# Adafruit_Feather_M4_Express.net
KiCad netlist of a schematic drawn in EAGLE
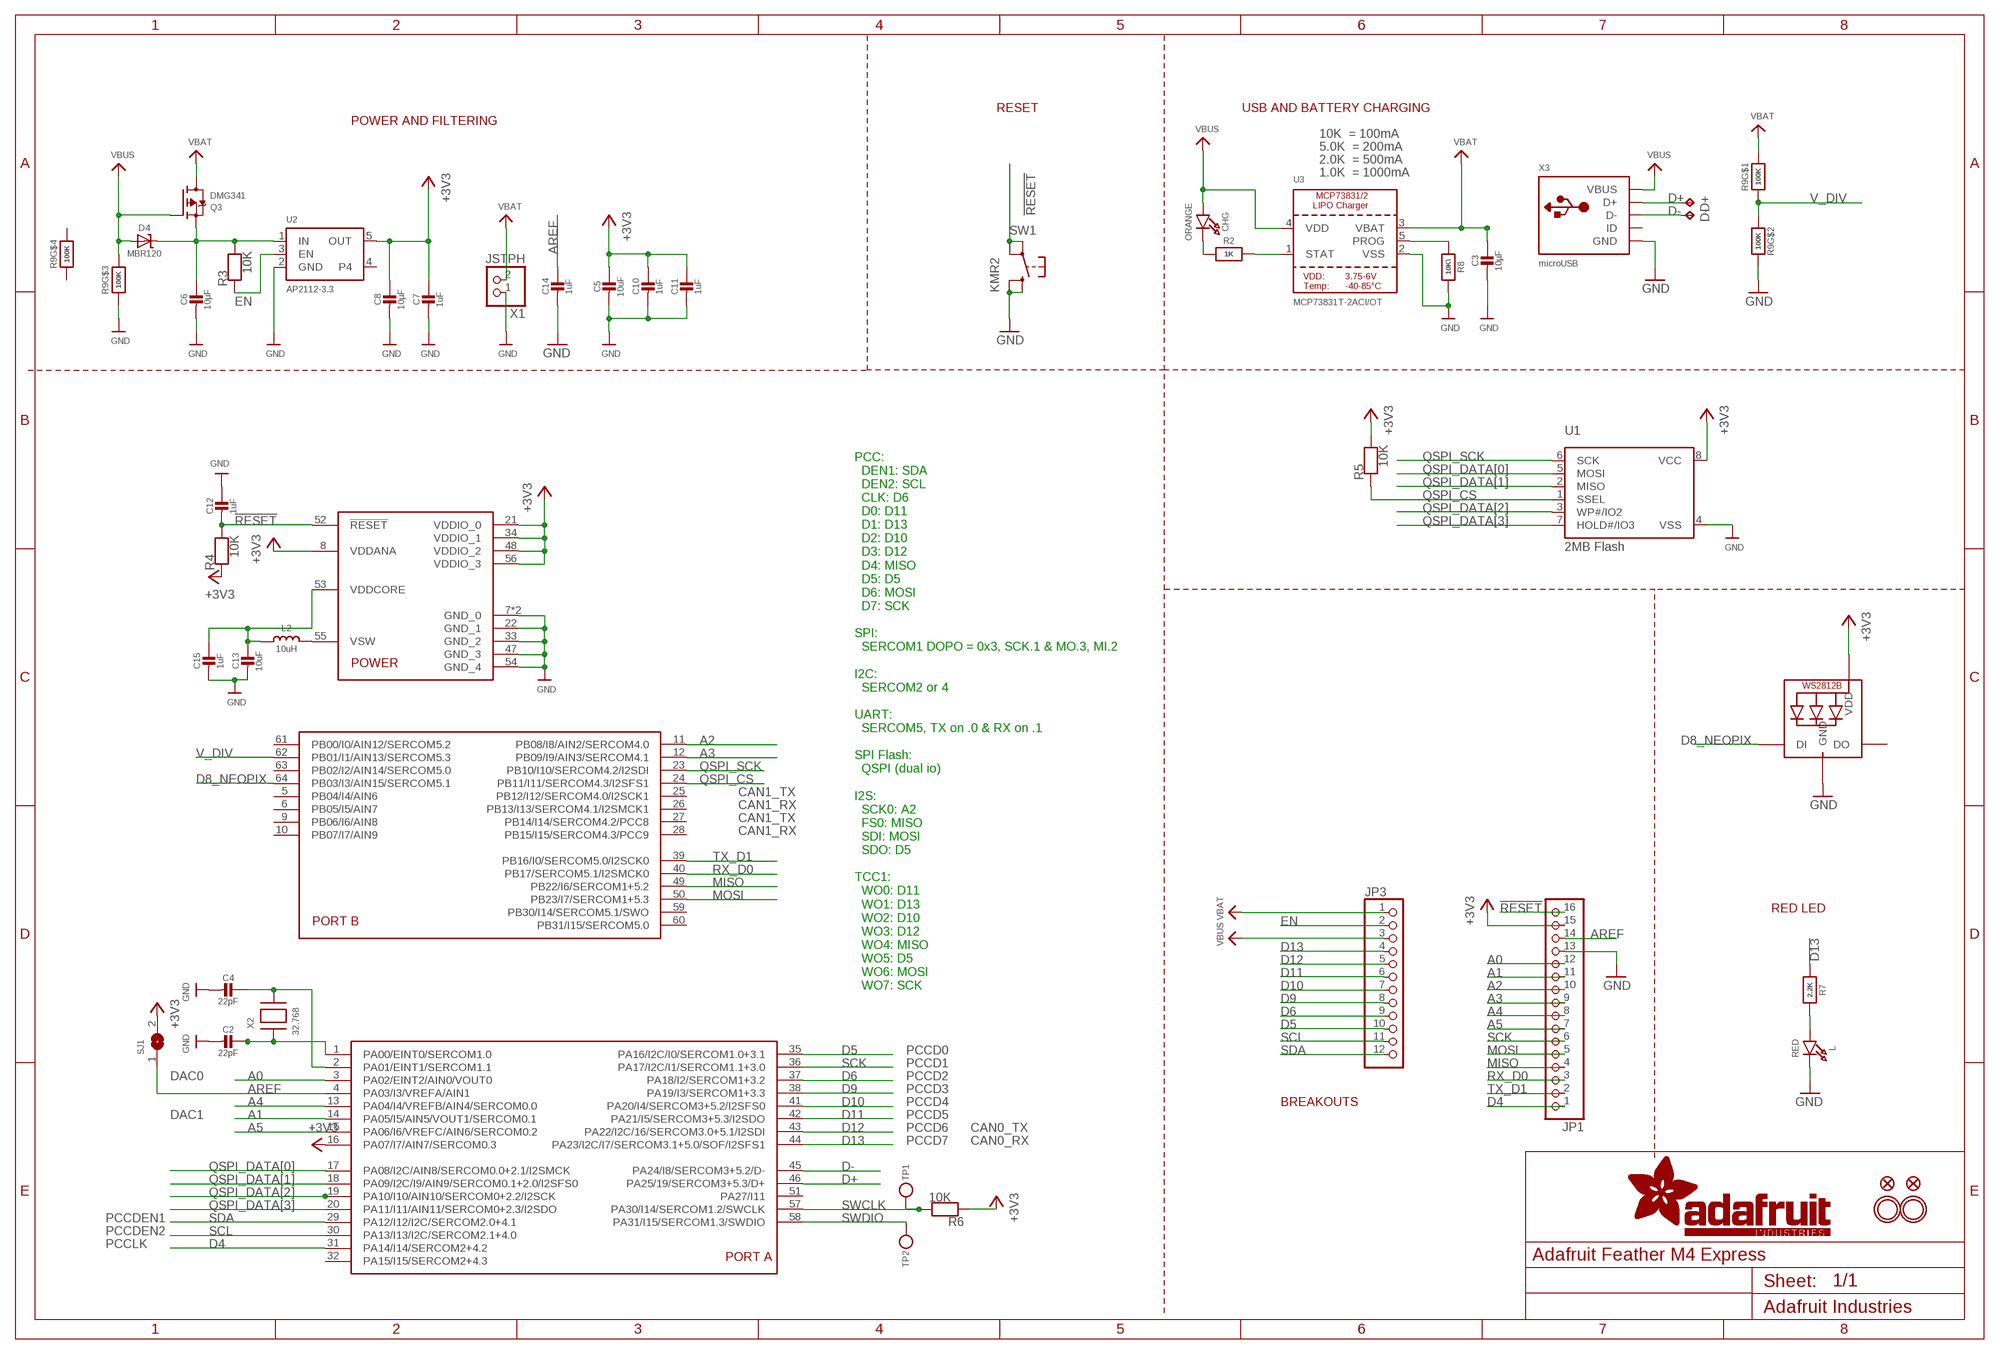
[diagram p0: schematic, sheet 1]

(export (version "E")
  (design (tool "Eeschema 10.0.6"))
  (components
    (comp (ref "C2")
      (value "22pF")
      (footprint "eagle-import:0603-NO")
      (libsource (lib "eagle-import") (part "CAP_CERAMIC0603_NO"))
    )
    (comp (ref "C3")
      (value "10µF")
      (footprint "eagle-import:0805-NO")
      (libsource (lib "eagle-import") (part "CAP_CERAMIC0805-NOOUTLINE"))
    )
    (comp (ref "C4")
      (value "22pF")
      (footprint "eagle-import:0603-NO")
      (libsource (lib "eagle-import") (part "CAP_CERAMIC0603_NO"))
    )
    (comp (ref "C5")
      (value "10uF")
      (footprint "eagle-import:0805-NO")
      (libsource (lib "eagle-import") (part "CAP_CERAMIC0805-NOOUTLINE"))
    )
    (comp (ref "C6")
      (value "10µF")
      (footprint "eagle-import:0805-NO")
      (libsource (lib "eagle-import") (part "CAP_CERAMIC0805-NOOUTLINE"))
    )
    (comp (ref "C7")
      (value "1uF")
      (footprint "eagle-import:0603-NO")
      (libsource (lib "eagle-import") (part "CAP_CERAMIC0603_NO"))
    )
    (comp (ref "C8")
      (value "10µF")
      (footprint "eagle-import:0805-NO")
      (libsource (lib "eagle-import") (part "CAP_CERAMIC0805-NOOUTLINE"))
    )
    (comp (ref "C10")
      (value "1uF")
      (footprint "eagle-import:0603-NO")
      (libsource (lib "eagle-import") (part "CAP_CERAMIC0603_NO"))
    )
    (comp (ref "C11")
      (value "1uF")
      (footprint "eagle-import:0603-NO")
      (libsource (lib "eagle-import") (part "CAP_CERAMIC0603_NO"))
    )
    (comp (ref "C12")
      (value "1uF")
      (footprint "eagle-import:0603-NO")
      (libsource (lib "eagle-import") (part "CAP_CERAMIC0603_NO"))
    )
    (comp (ref "C13")
      (value "10uF")
      (footprint "eagle-import:0805-NO")
      (libsource (lib "eagle-import") (part "CAP_CERAMIC0805-NOOUTLINE"))
    )
    (comp (ref "C14")
      (value "1uF")
      (footprint "eagle-import:0603-NO")
      (libsource (lib "eagle-import") (part "CAP_CERAMIC0603_NO"))
    )
    (comp (ref "C15")
      (value "1uF")
      (footprint "eagle-import:0603-NO")
      (libsource (lib "eagle-import") (part "CAP_CERAMIC0603_NO"))
    )
    (comp (ref "CHG")
      (value "ORANGE")
      (footprint "eagle-import:CHIPLED_0805_NOOUTLINE")
      (libsource (lib "eagle-import") (part "LED0805_NOOUTLINE"))
    )
    (comp (ref "D+")
      (value "TPB1,27")
      (footprint "eagle-import:B1,27")
      (libsource (lib "eagle-import") (part "TPB1,27"))
    )
    (comp (ref "D-")
      (value "TPB1,27")
      (footprint "eagle-import:B1,27")
      (libsource (lib "eagle-import") (part "TPB1,27"))
    )
    (comp (ref "D4")
      (value "MBR120")
      (footprint "eagle-import:SOD-123")
      (libsource (lib "eagle-import") (part "DIODE-SCHOTTKYSOD-123"))
    )
    (comp (ref "JP1")
      (value "HEADER-1X16ROUND")
      (footprint "eagle-import:1X16_ROUND")
      (libsource (lib "eagle-import") (part "HEADER-1X16ROUND"))
    )
    (comp (ref "JP3")
      (value "HEADER-1X12")
      (footprint "eagle-import:1X12_ROUND")
      (libsource (lib "eagle-import") (part "HEADER-1X12"))
    )
    (comp (ref "L")
      (value "RED")
      (footprint "eagle-import:CHIPLED_0805_NOOUTLINE")
      (libsource (lib "eagle-import") (part "LED0805_NOOUTLINE"))
    )
    (comp (ref "L2")
      (value "10uH")
      (footprint "eagle-import:INDUCTOR_1007")
      (libsource (lib "eagle-import") (part "INDUCTOR"))
    )
    (comp (ref "LED1")
      (value "WS2812B3535")
      (footprint "eagle-import:LED3535")
      (libsource (lib "eagle-import") (part "WS2812B3535"))
    )
    (comp (ref "Q3")
      (value "DMG341")
      (footprint "eagle-import:SOT23-R")
      (libsource (lib "eagle-import") (part "MOSFET-P"))
    )
    (comp (ref "R2")
      (value "1K")
      (footprint "eagle-import:0603-NO")
      (libsource (lib "eagle-import") (part "RESISTOR_0603_NOOUT"))
    )
    (comp (ref "R3")
      (value "10K")
      (footprint "eagle-import:0603-NO")
      (libsource (lib "eagle-import") (part "RESISTOR_0603_NOOUT"))
    )
    (comp (ref "R4")
      (value "10K")
      (footprint "eagle-import:0603-NO")
      (libsource (lib "eagle-import") (part "RESISTOR_0603_NOOUT"))
    )
    (comp (ref "R5")
      (value "10K")
      (footprint "eagle-import:0603-NO")
      (libsource (lib "eagle-import") (part "RESISTOR_0603_NOOUT"))
    )
    (comp (ref "R6")
      (value "10K")
      (footprint "eagle-import:0603-NO")
      (libsource (lib "eagle-import") (part "RESISTOR_0603_NOOUT"))
    )
    (comp (ref "R7")
      (value "2.2K")
      (footprint "eagle-import:0603-NO")
      (libsource (lib "eagle-import") (part "RESISTOR_0603_NOOUT"))
    )
    (comp (ref "R8")
      (value "10K\\")
      (footprint "eagle-import:0603-NO")
      (libsource (lib "eagle-import") (part "RESISTOR_0603_NOOUT"))
    )
    (comp (ref "R9")
      (value "100K")
      (footprint "eagle-import:RESPACK_4X0603_NO")
      (libsource (lib "eagle-import") (part "RESISTOR_4PACK_NO"))
    )
    (comp (ref "SJ1")
      (value "SOLDERJUMPERCLOSED")
      (footprint "eagle-import:SOLDERJUMPER_CLOSEDWIRE")
      (libsource (lib "eagle-import") (part "SOLDERJUMPERCLOSED"))
    )
    (comp (ref "SW1")
      (value "KMR2")
      (footprint "eagle-import:BTN_KMR2_4.6X2.8")
      (libsource (lib "eagle-import") (part "SWITCH_TACT_SMT4.6X2.8"))
    )
    (comp (ref "TP1")
      (value "TESTPOINTROUND1.5MM")
      (footprint "eagle-import:TESTPOINT_ROUND_1.5MM")
      (libsource (lib "eagle-import") (part "TESTPOINTROUND1.5MM"))
    )
    (comp (ref "TP2")
      (value "TESTPOINTROUND1.5MM")
      (footprint "eagle-import:TESTPOINT_ROUND_1.5MM")
      (libsource (lib "eagle-import") (part "TESTPOINTROUND1.5MM"))
    )
    (comp (ref "U$14")
      (value "ATSAMD51J")
      (footprint "eagle-import:PQFN64-1")
      (libsource (lib "eagle-import") (part "ATSAMD51J"))
    )
    (comp (ref "U$31")
      (value "MOUNTINGHOLE2.5")
      (footprint "eagle-import:MOUNTINGHOLE_2.5_PLATED")
      (libsource (lib "eagle-import") (part "MOUNTINGHOLE2.5"))
    )
    (comp (ref "U$32")
      (value "MOUNTINGHOLE2.5")
      (footprint "eagle-import:MOUNTINGHOLE_2.5_PLATED")
      (libsource (lib "eagle-import") (part "MOUNTINGHOLE2.5"))
    )
    (comp (ref "U$34")
      (value "FIDUCIAL_1MM")
      (footprint "eagle-import:FIDUCIAL_1MM")
      (libsource (lib "eagle-import") (part "FIDUCIAL_1MM"))
    )
    (comp (ref "U$35")
      (value "FIDUCIAL_1MM")
      (footprint "eagle-import:FIDUCIAL_1MM")
      (libsource (lib "eagle-import") (part "FIDUCIAL_1MM"))
    )
    (comp (ref "U1")
      (value "2MB Flash")
      (footprint "eagle-import:USON8")
      (libsource (lib "eagle-import") (part "SPIFLASH_8PINUX"))
    )
    (comp (ref "U2")
      (value "AP2112-3.3")
      (footprint "eagle-import:SOT23-5")
      (libsource (lib "eagle-import") (part "VREG_SOT23-5"))
    )
    (comp (ref "U3")
      (value "MCP73831T-2ACI/OT")
      (footprint "eagle-import:SOT23-5")
      (libsource (lib "eagle-import") (part "MCP73831/2"))
    )
    (comp (ref "X1")
      (value "JSTPH")
      (footprint "eagle-import:JSTPH2")
      (libsource (lib "eagle-import") (part "CON_JST_PH_2PIN"))
    )
    (comp (ref "X2")
      (value "32.768")
      (footprint "eagle-import:XTAL3215")
      (libsource (lib "eagle-import") (part "XTAL-3.2X1.5"))
    )
    (comp (ref "X3")
      (value "microUSB")
      (footprint "eagle-import:4UCONN_20329_V2")
      (libsource (lib "eagle-import") (part "USB_MICRO_20329_V2"))
    )
  )
  (nets
    (net (code "1") (name "+3V3") (class "Default")
      (node (ref "C10") (pin "1") (pinfunction "1_1") (pintype "passive"))
      (node (ref "C11") (pin "1") (pinfunction "1_1") (pintype "passive"))
      (node (ref "C5") (pin "1") (pinfunction "1_1") (pintype "passive"))
      (node (ref "C7") (pin "1") (pinfunction "1_1") (pintype "passive"))
      (node (ref "C8") (pin "1") (pinfunction "1_1") (pintype "passive"))
      (node (ref "JP1") (pin "15") (pinfunction "15_15") (pintype "passive"))
      (node (ref "LED1") (pin "2") (pinfunction "VDD_2") (pintype "power_in"))
      (node (ref "R4") (pin "1") (pinfunction "1_1") (pintype "passive"))
      (node (ref "R5") (pin "2") (pinfunction "2_2") (pintype "passive"))
      (node (ref "R6") (pin "1") (pinfunction "1_1") (pintype "passive"))
      (node (ref "SJ1") (pin "2") (pinfunction "2_2") (pintype "passive"))
      (node (ref "U$14") (pin "16") (pinfunction "PA07/I7/AIN7/SERCOM0.3_16") (pintype "bidirectional"))
      (node (ref "U$14") (pin "21") (pinfunction "VDDIO_0_21") (pintype "bidirectional"))
      (node (ref "U$14") (pin "34") (pinfunction "VDDIO_1_34") (pintype "bidirectional"))
      (node (ref "U$14") (pin "48") (pinfunction "VDDIO_2_48") (pintype "bidirectional"))
      (node (ref "U$14") (pin "56") (pinfunction "VDDIO_3_56") (pintype "bidirectional"))
      (node (ref "U$14") (pin "8") (pinfunction "VDDANA_8") (pintype "bidirectional"))
      (node (ref "U1") (pin "8") (pinfunction "VCC_8") (pintype "bidirectional"))
      (node (ref "U2") (pin "5") (pinfunction "OUT_5") (pintype "power_in"))
    )
    (net (code "2") (name "/A0") (class "Default")
      (node (ref "JP1") (pin "12") (pinfunction "12_12") (pintype "passive"))
      (node (ref "U$14") (pin "3") (pinfunction "PA02/EINT2/AIN0/VOUT0_3") (pintype "bidirectional"))
    )
    (net (code "3") (name "/A1") (class "Default")
      (node (ref "JP1") (pin "11") (pinfunction "11_11") (pintype "passive"))
      (node (ref "U$14") (pin "14") (pinfunction "PA05/I5/AIN5/VOUT1/SERCOM0.1_14") (pintype "bidirectional"))
    )
    (net (code "4") (name "/A2") (class "Default")
      (node (ref "JP1") (pin "10") (pinfunction "10_10") (pintype "passive"))
      (node (ref "U$14") (pin "11") (pinfunction "PB08/I8/AIN2/SERCOM4.0_11") (pintype "bidirectional"))
    )
    (net (code "5") (name "/A3") (class "Default")
      (node (ref "JP1") (pin "9") (pinfunction "9_9") (pintype "passive"))
      (node (ref "U$14") (pin "12") (pinfunction "PB09/I9/AIN3/SERCOM4.1_12") (pintype "bidirectional"))
    )
    (net (code "6") (name "/A4") (class "Default")
      (node (ref "JP1") (pin "8") (pinfunction "8_8") (pintype "passive"))
      (node (ref "U$14") (pin "13") (pinfunction "PA04/I4/VREFB/AIN4/SERCOM0.0_13") (pintype "bidirectional"))
    )
    (net (code "7") (name "/A5") (class "Default")
      (node (ref "JP1") (pin "7") (pinfunction "7_7") (pintype "passive"))
      (node (ref "U$14") (pin "15") (pinfunction "PA06/I6/VREFC/AIN6/SERCOM0.2_15") (pintype "bidirectional"))
    )
    (net (code "8") (name "/AREF") (class "Default")
      (node (ref "C14") (pin "1") (pinfunction "1_1") (pintype "passive"))
      (node (ref "JP1") (pin "14") (pinfunction "14_14") (pintype "passive"))
      (node (ref "SJ1") (pin "1") (pinfunction "1_1") (pintype "passive"))
      (node (ref "U$14") (pin "4") (pinfunction "PA03/I3/VREFA/AIN1_4") (pintype "bidirectional"))
    )
    (net (code "9") (name "/D+") (class "Default")
      (node (ref "D+") (pin "TP") (pinfunction "TP_TP") (pintype "input"))
      (node (ref "U$14") (pin "46") (pinfunction "PA25/19/SERCOM3+5.3/D+_46") (pintype "bidirectional"))
      (node (ref "X3") (pin "D+") (pinfunction "D+_D+") (pintype "bidirectional"))
    )
    (net (code "10") (name "/D-") (class "Default")
      (node (ref "D-") (pin "TP") (pinfunction "TP_TP") (pintype "input"))
      (node (ref "U$14") (pin "45") (pinfunction "PA24/I8/SERCOM3+5.2/D-_45") (pintype "bidirectional"))
      (node (ref "X3") (pin "D-") (pinfunction "D-_D-") (pintype "bidirectional"))
    )
    (net (code "11") (name "/D4") (class "Default")
      (node (ref "JP1") (pin "1") (pinfunction "1_1") (pintype "passive"))
      (node (ref "U$14") (pin "31") (pinfunction "PA14/I14/SERCOM2+4.2_31") (pintype "bidirectional"))
    )
    (net (code "12") (name "/D5") (class "Default")
      (node (ref "JP3") (pin "10") (pinfunction "10_10") (pintype "passive"))
      (node (ref "U$14") (pin "35") (pinfunction "PA16/I2C/I0/SERCOM1.0+3.1_35") (pintype "bidirectional"))
    )
    (net (code "13") (name "/D6") (class "Default")
      (node (ref "JP3") (pin "9") (pinfunction "9_9") (pintype "passive"))
      (node (ref "U$14") (pin "37") (pinfunction "PA18/I2/SERCOM1+3.2_37") (pintype "bidirectional"))
    )
    (net (code "14") (name "/D8_NEOPIX") (class "Default")
      (node (ref "LED1") (pin "1") (pinfunction "DI_1") (pintype "input"))
      (node (ref "U$14") (pin "64") (pinfunction "PB03/I3/AIN15/SERCOM5.1_64") (pintype "bidirectional"))
    )
    (net (code "15") (name "/D9") (class "Default")
      (node (ref "JP3") (pin "8") (pinfunction "8_8") (pintype "passive"))
      (node (ref "U$14") (pin "38") (pinfunction "PA19/I3/SERCOM1+3.3_38") (pintype "bidirectional"))
    )
    (net (code "16") (name "/D10") (class "Default")
      (node (ref "JP3") (pin "7") (pinfunction "7_7") (pintype "passive"))
      (node (ref "U$14") (pin "41") (pinfunction "PA20/I4/SERCOM3+5.2/I2SFS0_41") (pintype "bidirectional"))
    )
    (net (code "17") (name "/D11") (class "Default")
      (node (ref "JP3") (pin "6") (pinfunction "6_6") (pintype "passive"))
      (node (ref "U$14") (pin "42") (pinfunction "PA21/I5/SERCOM3+5.3/I2SDO_42") (pintype "bidirectional"))
    )
    (net (code "18") (name "/D12") (class "Default")
      (node (ref "JP3") (pin "5") (pinfunction "5_5") (pintype "passive"))
      (node (ref "U$14") (pin "43") (pinfunction "PA22/I2C/16/SERCOM3.0+5.1/I2SDI_43") (pintype "bidirectional"))
    )
    (net (code "19") (name "/D13") (class "Default")
      (node (ref "JP3") (pin "4") (pinfunction "4_4") (pintype "passive"))
      (node (ref "R7") (pin "1") (pinfunction "1_1") (pintype "passive"))
      (node (ref "U$14") (pin "44") (pinfunction "PA23/I2C/I7/SERCOM3.1+5.0/SOF/I2SFS1_44") (pintype "bidirectional"))
    )
    (net (code "20") (name "/EN") (class "Default")
      (node (ref "JP3") (pin "2") (pinfunction "2_2") (pintype "passive"))
      (node (ref "R3") (pin "1") (pinfunction "1_1") (pintype "passive"))
      (node (ref "U2") (pin "3") (pinfunction "EN_3") (pintype "input"))
    )
    (net (code "21") (name "/MISO") (class "Default")
      (node (ref "JP1") (pin "4") (pinfunction "4_4") (pintype "passive"))
      (node (ref "U$14") (pin "49") (pinfunction "PB22/I6/SERCOM1+5.2_49") (pintype "bidirectional"))
    )
    (net (code "22") (name "/MOSI") (class "Default")
      (node (ref "JP1") (pin "5") (pinfunction "5_5") (pintype "passive"))
      (node (ref "U$14") (pin "50") (pinfunction "PB23/I7/SERCOM1+5.3_50") (pintype "bidirectional"))
    )
    (net (code "23") (name "/QSPI_CS") (class "Default")
      (node (ref "R5") (pin "1") (pinfunction "1_1") (pintype "passive"))
      (node (ref "U$14") (pin "24") (pinfunction "PB11/I11/SERCOM4.3/I2SFS1_24") (pintype "bidirectional"))
      (node (ref "U1") (pin "1") (pinfunction "SSEL_1") (pintype "bidirectional"))
    )
    (net (code "24") (name "/QSPI_DATA[0]") (class "Default")
      (node (ref "U$14") (pin "17") (pinfunction "PA08/I2C/AIN8/SERCOM0.0+2.1/I2SMCK_17") (pintype "bidirectional"))
      (node (ref "U1") (pin "5") (pinfunction "MOSI_5") (pintype "bidirectional"))
    )
    (net (code "25") (name "/QSPI_DATA[1]") (class "Default")
      (node (ref "U$14") (pin "18") (pinfunction "PA09/I2C/I9/AIN9/SERCOM0.1+2.0/I2SFS0_18") (pintype "bidirectional"))
      (node (ref "U1") (pin "2") (pinfunction "MISO_2") (pintype "bidirectional"))
    )
    (net (code "26") (name "/QSPI_DATA[2]") (class "Default")
      (node (ref "U$14") (pin "19") (pinfunction "PA10/I10/AIN10/SERCOM0+2.2/I2SCK_19") (pintype "bidirectional"))
      (node (ref "U1") (pin "3") (pinfunction "WP#/IO2_3") (pintype "bidirectional"))
    )
    (net (code "27") (name "/QSPI_DATA[3]") (class "Default")
      (node (ref "U$14") (pin "20") (pinfunction "PA11/I11/AIN11/SERCOM0+2.3/I2SDO_20") (pintype "bidirectional"))
      (node (ref "U1") (pin "7") (pinfunction "HOLD#/IO3_7") (pintype "bidirectional"))
    )
    (net (code "28") (name "/QSPI_SCK") (class "Default")
      (node (ref "U$14") (pin "23") (pinfunction "PB10/I10/SERCOM4.2/I2SDI_23") (pintype "bidirectional"))
      (node (ref "U1") (pin "6") (pinfunction "SCK_6") (pintype "bidirectional"))
    )
    (net (code "29") (name "/RX_D0") (class "Default")
      (node (ref "JP1") (pin "3") (pinfunction "3_3") (pintype "passive"))
      (node (ref "U$14") (pin "40") (pinfunction "PB17/SERCOM5.1/I2SMCK0_40") (pintype "bidirectional"))
    )
    (net (code "30") (name "/SCK") (class "Default")
      (node (ref "JP1") (pin "6") (pinfunction "6_6") (pintype "passive"))
      (node (ref "U$14") (pin "36") (pinfunction "PA17/I2C/I1/SERCOM1.1+3.0_36") (pintype "bidirectional"))
    )
    (net (code "31") (name "/SCL") (class "Default")
      (node (ref "JP3") (pin "11") (pinfunction "11_11") (pintype "passive"))
      (node (ref "U$14") (pin "30") (pinfunction "PA13/I13/I2C/SERCOM2.1+4.0_30") (pintype "bidirectional"))
    )
    (net (code "32") (name "/SDA") (class "Default")
      (node (ref "JP3") (pin "12") (pinfunction "12_12") (pintype "passive"))
      (node (ref "U$14") (pin "29") (pinfunction "PA12/I12/I2C/SERCOM2.0+4.1_29") (pintype "bidirectional"))
    )
    (net (code "33") (name "/SWCLK") (class "Default")
      (node (ref "R6") (pin "2") (pinfunction "2_2") (pintype "passive"))
      (node (ref "TP1") (pin "P$1") (pinfunction "P$1_P$1") (pintype "bidirectional"))
      (node (ref "U$14") (pin "57") (pinfunction "PA30/I14/SERCOM1.2/SWCLK_57") (pintype "bidirectional"))
    )
    (net (code "34") (name "/SWDIO") (class "Default")
      (node (ref "TP2") (pin "P$1") (pinfunction "P$1_P$1") (pintype "bidirectional"))
      (node (ref "U$14") (pin "58") (pinfunction "PA31/I15/SERCOM1.3/SWDIO_58") (pintype "bidirectional"))
    )
    (net (code "35") (name "/TX_D1") (class "Default")
      (node (ref "JP1") (pin "2") (pinfunction "2_2") (pintype "passive"))
      (node (ref "U$14") (pin "39") (pinfunction "PB16/I0/SERCOM5.0/I2SCK0_39") (pintype "bidirectional"))
    )
    (net (code "36") (name "/V_DIV") (class "Default")
      (node (ref "R9") (pin "1") (pinfunction "1_1") (pintype "passive"))
      (node (ref "R9") (pin "2") (pinfunction "1_2") (pintype "passive"))
      (node (ref "U$14") (pin "62") (pinfunction "PB01/I1/AIN13/SERCOM5.3_62") (pintype "bidirectional"))
    )
    (net (code "37") (name "/~{RESET}") (class "Default")
      (node (ref "C12") (pin "2") (pinfunction "2_2") (pintype "passive"))
      (node (ref "JP1") (pin "16") (pinfunction "16_16") (pintype "passive"))
      (node (ref "R4") (pin "2") (pinfunction "2_2") (pintype "passive"))
      (node (ref "SW1") (pin "A") (pinfunction "P_A") (pintype "passive"))
      (node (ref "SW1") (pin "A'") (pinfunction "P1_A'") (pintype "passive"))
      (node (ref "U$14") (pin "52") (pinfunction "~{RESET}_52") (pintype "bidirectional"))
    )
    (net (code "38") (name "GND") (class "Default")
      (node (ref "C10") (pin "2") (pinfunction "2_2") (pintype "passive"))
      (node (ref "C11") (pin "2") (pinfunction "2_2") (pintype "passive"))
      (node (ref "C12") (pin "1") (pinfunction "1_1") (pintype "passive"))
      (node (ref "C13") (pin "2") (pinfunction "2_2") (pintype "passive"))
      (node (ref "C14") (pin "2") (pinfunction "2_2") (pintype "passive"))
      (node (ref "C15") (pin "2") (pinfunction "2_2") (pintype "passive"))
      (node (ref "C2") (pin "2") (pinfunction "2_2") (pintype "passive"))
      (node (ref "C3") (pin "2") (pinfunction "2_2") (pintype "passive"))
      (node (ref "C4") (pin "2") (pinfunction "2_2") (pintype "passive"))
      (node (ref "C5") (pin "2") (pinfunction "2_2") (pintype "passive"))
      (node (ref "C6") (pin "2") (pinfunction "2_2") (pintype "passive"))
      (node (ref "C7") (pin "2") (pinfunction "2_2") (pintype "passive"))
      (node (ref "C8") (pin "2") (pinfunction "2_2") (pintype "passive"))
      (node (ref "JP1") (pin "13") (pinfunction "13_13") (pintype "passive"))
      (node (ref "L") (pin "C") (pinfunction "C_C") (pintype "passive"))
      (node (ref "LED1") (pin "4") (pinfunction "GND_4") (pintype "power_in"))
      (node (ref "R8") (pin "2") (pinfunction "2_2") (pintype "passive"))
      (node (ref "R9") (pin "3") (pinfunction "1_3") (pintype "passive"))
      (node (ref "R9") (pin "7") (pinfunction "2_7") (pintype "passive"))
      (node (ref "SW1") (pin "B") (pinfunction "S_B") (pintype "passive"))
      (node (ref "SW1") (pin "B'") (pinfunction "S1_B'") (pintype "passive"))
      (node (ref "U$14") (pin "22") (pinfunction "GND_1_22") (pintype "bidirectional"))
      (node (ref "U$14") (pin "33") (pinfunction "GND_2_33") (pintype "bidirectional"))
      (node (ref "U$14") (pin "47") (pinfunction "GND_3_47") (pintype "bidirectional"))
      (node (ref "U$14") (pin "54") (pinfunction "GND_4_54") (pintype "bidirectional"))
      (node (ref "U$14") (pin "7") (pinfunction "GND_0_7") (pintype "bidirectional"))
      (node (ref "U$14") (pin "EXP") (pinfunction "GND_0_EXP") (pintype "bidirectional"))
      (node (ref "U1") (pin "4") (pinfunction "VSS_4") (pintype "bidirectional"))
      (node (ref "U2") (pin "2") (pinfunction "GND_2") (pintype "power_in"))
      (node (ref "U3") (pin "2") (pinfunction "VSS_2") (pintype "power_in"))
      (node (ref "X1") (pin "1") (pinfunction "1_1") (pintype "passive"))
      (node (ref "X3") (pin "BASE@1") (pinfunction "GND_BASE@1") (pintype "power_in"))
      (node (ref "X3") (pin "BASE@2") (pinfunction "GND_BASE@2") (pintype "power_in"))
      (node (ref "X3") (pin "GND") (pinfunction "GND_GND") (pintype "power_in"))
      (node (ref "X3") (pin "SPRT@1") (pinfunction "GND_SPRT@1") (pintype "power_in"))
      (node (ref "X3") (pin "SPRT@2") (pinfunction "GND_SPRT@2") (pintype "power_in"))
      (node (ref "X3") (pin "SPRT@3") (pinfunction "GND_SPRT@3") (pintype "power_in"))
      (node (ref "X3") (pin "SPRT@4") (pinfunction "GND_SPRT@4") (pintype "power_in"))
    )
    (net (code "39") (name "Net-(CHG-PadC)") (class "Default")
      (node (ref "CHG") (pin "C") (pinfunction "C_C") (pintype "passive"))
      (node (ref "R2") (pin "1") (pinfunction "1_1") (pintype "passive"))
    )
    (net (code "40") (name "Net-(L-PadA)") (class "Default")
      (node (ref "L") (pin "A") (pinfunction "A_A") (pintype "passive"))
      (node (ref "R7") (pin "2") (pinfunction "2_2") (pintype "passive"))
    )
    (net (code "41") (name "Net-(L2-1)") (class "Default")
      (node (ref "C13") (pin "1") (pinfunction "1_1") (pintype "passive"))
      (node (ref "C15") (pin "1") (pinfunction "1_1") (pintype "passive"))
      (node (ref "L2") (pin "P$1") (pinfunction "1_P$1") (pintype "passive"))
      (node (ref "U$14") (pin "53") (pinfunction "VDDCORE_53") (pintype "bidirectional"))
    )
    (net (code "42") (name "Net-(L2-2)") (class "Default")
      (node (ref "L2") (pin "P$2") (pinfunction "2_P$2") (pintype "passive"))
      (node (ref "U$14") (pin "55") (pinfunction "VSW_55") (pintype "bidirectional"))
    )
    (net (code "43") (name "Net-(Q3-S)") (class "Default")
      (node (ref "C6") (pin "1") (pinfunction "1_1") (pintype "passive"))
      (node (ref "D4") (pin "C") (pinfunction "C_C") (pintype "passive"))
      (node (ref "Q3") (pin "2") (pinfunction "S_2") (pintype "passive"))
      (node (ref "R3") (pin "2") (pinfunction "2_2") (pintype "passive"))
      (node (ref "U2") (pin "1") (pinfunction "IN_1") (pintype "power_in"))
    )
    (net (code "44") (name "Net-(U$14A-PA00{slash}EINT0{slash}SERCOM1.0)") (class "Default")
      (node (ref "C2") (pin "1") (pinfunction "1_1") (pintype "passive"))
      (node (ref "U$14") (pin "1") (pinfunction "PA00/EINT0/SERCOM1.0_1") (pintype "bidirectional"))
      (node (ref "X2") (pin "P$1") (pinfunction "P$1_P$1") (pintype "bidirectional"))
    )
    (net (code "45") (name "Net-(U$14A-PA01{slash}EINT1{slash}SERCOM1.1)") (class "Default")
      (node (ref "C4") (pin "1") (pinfunction "1_1") (pintype "passive"))
      (node (ref "U$14") (pin "2") (pinfunction "PA01/EINT1/SERCOM1.1_2") (pintype "bidirectional"))
      (node (ref "X2") (pin "P$2") (pinfunction "P$2_P$2") (pintype "bidirectional"))
    )
    (net (code "46") (name "Net-(U3-PROG)") (class "Default")
      (node (ref "R8") (pin "1") (pinfunction "1_1") (pintype "passive"))
      (node (ref "U3") (pin "5") (pinfunction "PROG_5") (pintype "input"))
    )
    (net (code "47") (name "Net-(U3-STAT)") (class "Default")
      (node (ref "R2") (pin "2") (pinfunction "2_2") (pintype "passive"))
      (node (ref "U3") (pin "1") (pinfunction "STAT_1") (pintype "output"))
    )
    (net (code "48") (name "VBAT") (class "Default")
      (node (ref "C3") (pin "1") (pinfunction "1_1") (pintype "passive"))
      (node (ref "JP3") (pin "1") (pinfunction "1_1") (pintype "passive"))
      (node (ref "Q3") (pin "3") (pinfunction "D_3") (pintype "passive"))
      (node (ref "R9") (pin "8") (pinfunction "2_8") (pintype "passive"))
      (node (ref "U3") (pin "3") (pinfunction "VBAT_3") (pintype "power_in"))
      (node (ref "X1") (pin "2") (pinfunction "2_2") (pintype "passive"))
    )
    (net (code "49") (name "VBUS") (class "Default")
      (node (ref "CHG") (pin "A") (pinfunction "A_A") (pintype "passive"))
      (node (ref "D4") (pin "A") (pinfunction "A_A") (pintype "passive"))
      (node (ref "JP3") (pin "3") (pinfunction "3_3") (pintype "passive"))
      (node (ref "Q3") (pin "1") (pinfunction "G_1") (pintype "passive"))
      (node (ref "R9") (pin "6") (pinfunction "2_6") (pintype "passive"))
      (node (ref "U3") (pin "4") (pinfunction "VDD_4") (pintype "power_in"))
      (node (ref "X3") (pin "VBUS") (pinfunction "VBUS_VBUS") (pintype "power_in"))
    )
    (net (code "50") (name "unconnected-(LED1-DO-Pad3)") (class "Default")
      (node (ref "LED1") (pin "3") (pinfunction "DO_3") (pintype "output"))
    )
    (net (code "51") (name "unconnected-(R9D-1-Pad4)") (class "Default")
      (node (ref "R9") (pin "4") (pinfunction "1_4") (pintype "passive"))
    )
    (net (code "52") (name "unconnected-(R9D-2-Pad5)") (class "Default")
      (node (ref "R9") (pin "5") (pinfunction "2_5") (pintype "passive"))
    )
    (net (code "53") (name "unconnected-(U$14A-PA15{slash}I15{slash}SERCOM2+4.3-Pad32)") (class "Default")
      (node (ref "U$14") (pin "32") (pinfunction "PA15/I15/SERCOM2+4.3_32") (pintype "bidirectional"))
    )
    (net (code "54") (name "unconnected-(U$14A-PA27{slash}I11-Pad51)") (class "Default")
      (node (ref "U$14") (pin "51") (pinfunction "PA27/I11_51") (pintype "bidirectional"))
    )
    (net (code "55") (name "unconnected-(U$14B-PB00{slash}I0{slash}AIN12{slash}SERCOM5.2-Pad61)") (class "Default")
      (node (ref "U$14") (pin "61") (pinfunction "PB00/I0/AIN12/SERCOM5.2_61") (pintype "bidirectional"))
    )
    (net (code "56") (name "unconnected-(U$14B-PB02{slash}I2{slash}AIN14{slash}SERCOM5.0-Pad63)") (class "Default")
      (node (ref "U$14") (pin "63") (pinfunction "PB02/I2/AIN14/SERCOM5.0_63") (pintype "bidirectional"))
    )
    (net (code "57") (name "unconnected-(U$14B-PB04{slash}I4{slash}AIN6-Pad5)") (class "Default")
      (node (ref "U$14") (pin "5") (pinfunction "PB04/I4/AIN6_5") (pintype "bidirectional"))
    )
    (net (code "58") (name "unconnected-(U$14B-PB05{slash}I5{slash}AIN7-Pad6)") (class "Default")
      (node (ref "U$14") (pin "6") (pinfunction "PB05/I5/AIN7_6") (pintype "bidirectional"))
    )
    (net (code "59") (name "unconnected-(U$14B-PB06{slash}I6{slash}AIN8-Pad9)") (class "Default")
      (node (ref "U$14") (pin "9") (pinfunction "PB06/I6/AIN8_9") (pintype "bidirectional"))
    )
    (net (code "60") (name "unconnected-(U$14B-PB07{slash}I7{slash}AIN9-Pad10)") (class "Default")
      (node (ref "U$14") (pin "10") (pinfunction "PB07/I7/AIN9_10") (pintype "bidirectional"))
    )
    (net (code "61") (name "unconnected-(U$14B-PB12{slash}I12{slash}SERCOM4.0{slash}I2SCK1-Pad25)") (class "Default")
      (node (ref "U$14") (pin "25") (pinfunction "PB12/I12/SERCOM4.0/I2SCK1_25") (pintype "bidirectional"))
    )
    (net (code "62") (name "unconnected-(U$14B-PB13{slash}I13{slash}SERCOM4.1{slash}I2SMCK1-Pad26)") (class "Default")
      (node (ref "U$14") (pin "26") (pinfunction "PB13/I13/SERCOM4.1/I2SMCK1_26") (pintype "bidirectional"))
    )
    (net (code "63") (name "unconnected-(U$14B-PB14{slash}I14{slash}SERCOM4.2{slash}PCC8-Pad27)") (class "Default")
      (node (ref "U$14") (pin "27") (pinfunction "PB14/I14/SERCOM4.2/PCC8_27") (pintype "bidirectional"))
    )
    (net (code "64") (name "unconnected-(U$14B-PB15{slash}I15{slash}SERCOM4.3{slash}PCC9-Pad28)") (class "Default")
      (node (ref "U$14") (pin "28") (pinfunction "PB15/I15/SERCOM4.3/PCC9_28") (pintype "bidirectional"))
    )
    (net (code "65") (name "unconnected-(U$14B-PB30{slash}I14{slash}SERCOM5.1{slash}SWO-Pad59)") (class "Default")
      (node (ref "U$14") (pin "59") (pinfunction "PB30/I14/SERCOM5.1/SWO_59") (pintype "bidirectional"))
    )
    (net (code "66") (name "unconnected-(U$14B-PB31{slash}I15{slash}SERCOM5.0-Pad60)") (class "Default")
      (node (ref "U$14") (pin "60") (pinfunction "PB31/I15/SERCOM5.0_60") (pintype "bidirectional"))
    )
    (net (code "67") (name "unconnected-(U2-P4-Pad4)") (class "Default")
      (node (ref "U2") (pin "4") (pinfunction "P4_4") (pintype "bidirectional"))
    )
    (net (code "68") (name "unconnected-(X3-PadID)") (class "Default")
      (node (ref "X3") (pin "ID") (pinfunction "ID_ID") (pintype "bidirectional"))
    )
  )
)
